# SN74ALVC164245_Level_Shifter.net
KiCad netlist of a schematic drawn in EAGLE
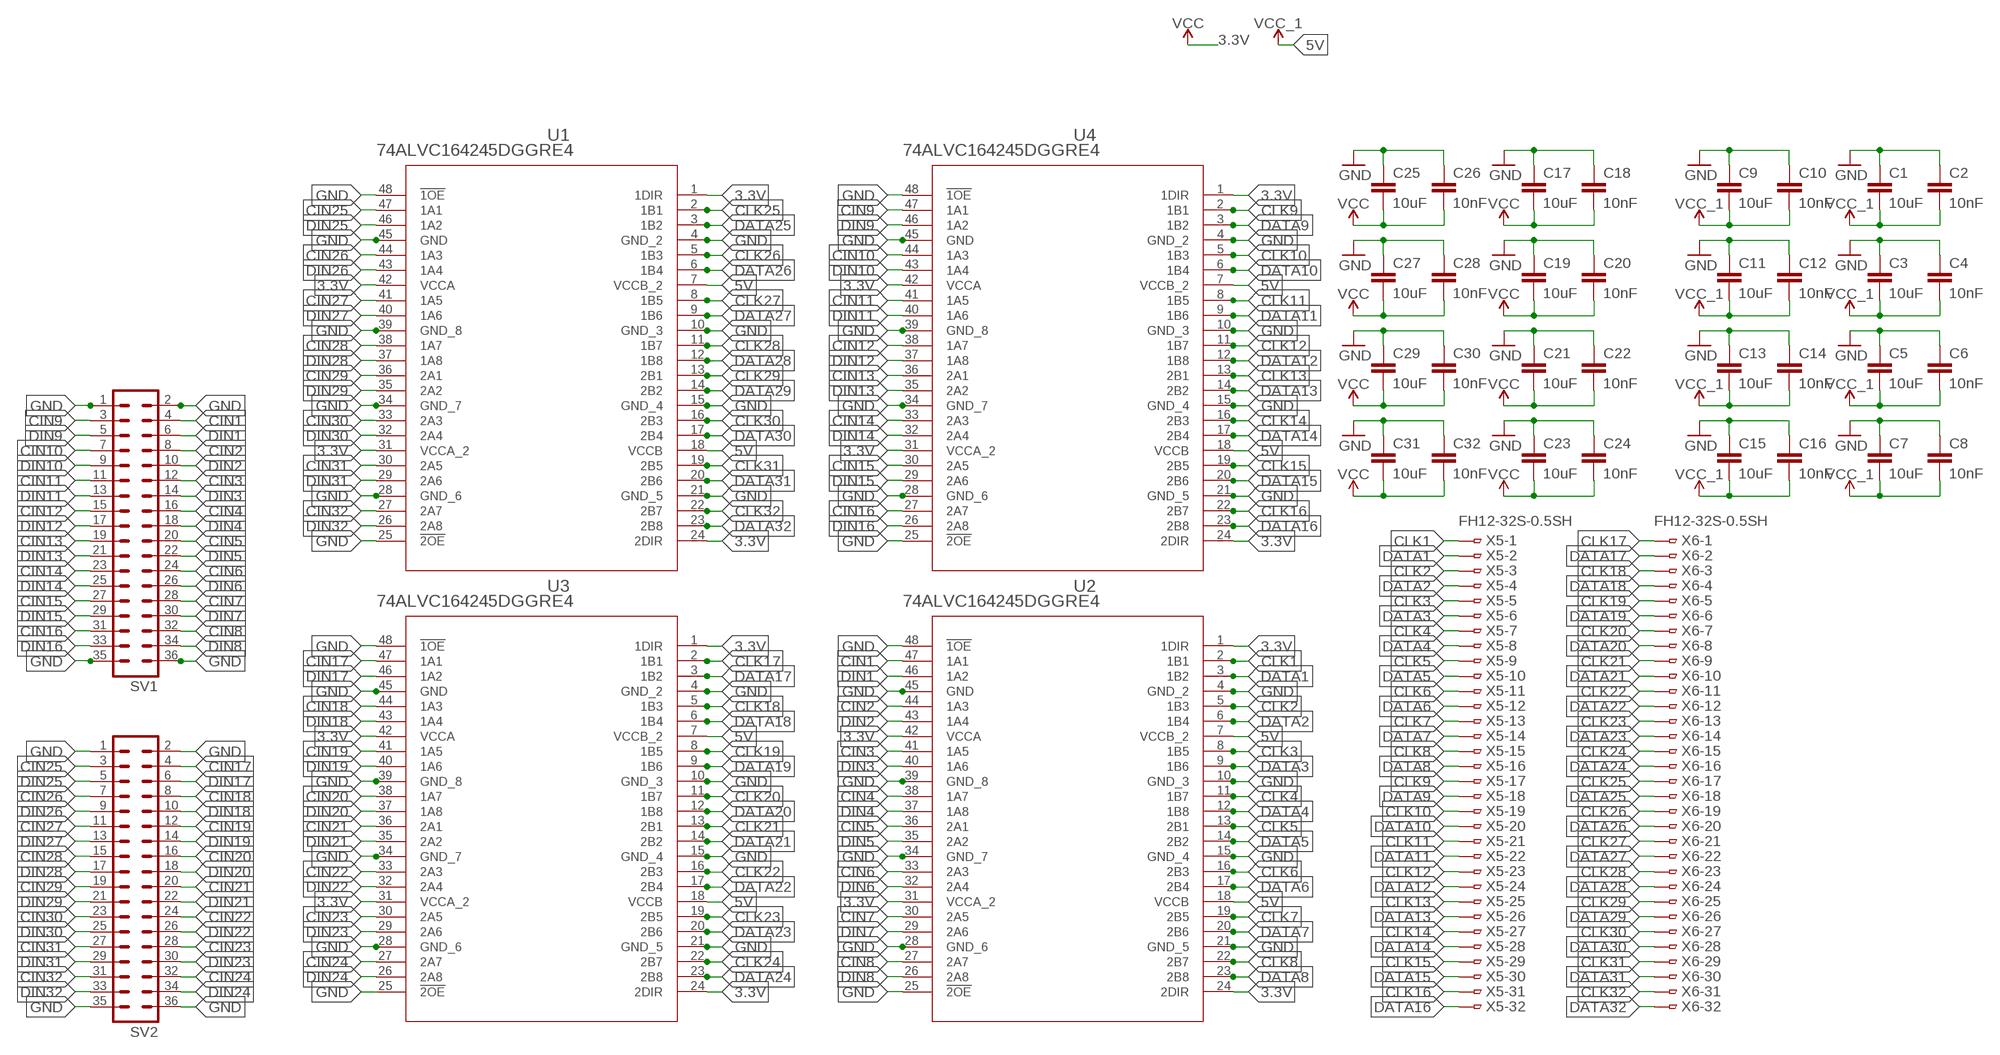
[diagram p0: schematic, sheet 1]

(export (version "E")
  (design (tool "Eeschema 10.0.6"))
  (components
    (comp (ref "C1")
      (value "10uF")
      (footprint "eagle-import:0402-TIGHT")
      (libsource (lib "eagle-import") (part "10UF-0402T-6.3V-20%"))
    )
    (comp (ref "C2")
      (value "10nF")
      (footprint "eagle-import:0402-TIGHT")
      (libsource (lib "eagle-import") (part "10NF-0402T-25V-10%"))
    )
    (comp (ref "C3")
      (value "10uF")
      (footprint "eagle-import:0402-TIGHT")
      (libsource (lib "eagle-import") (part "10UF-0402T-6.3V-20%"))
    )
    (comp (ref "C4")
      (value "10nF")
      (footprint "eagle-import:0402-TIGHT")
      (libsource (lib "eagle-import") (part "10NF-0402T-25V-10%"))
    )
    (comp (ref "C5")
      (value "10uF")
      (footprint "eagle-import:0402-TIGHT")
      (libsource (lib "eagle-import") (part "10UF-0402T-6.3V-20%"))
    )
    (comp (ref "C6")
      (value "10nF")
      (footprint "eagle-import:0402-TIGHT")
      (libsource (lib "eagle-import") (part "10NF-0402T-25V-10%"))
    )
    (comp (ref "C7")
      (value "10uF")
      (footprint "eagle-import:0402-TIGHT")
      (libsource (lib "eagle-import") (part "10UF-0402T-6.3V-20%"))
    )
    (comp (ref "C8")
      (value "10nF")
      (footprint "eagle-import:0402-TIGHT")
      (libsource (lib "eagle-import") (part "10NF-0402T-25V-10%"))
    )
    (comp (ref "C9")
      (value "10uF")
      (footprint "eagle-import:0402-TIGHT")
      (libsource (lib "eagle-import") (part "10UF-0402T-6.3V-20%"))
    )
    (comp (ref "C10")
      (value "10nF")
      (footprint "eagle-import:0402-TIGHT")
      (libsource (lib "eagle-import") (part "10NF-0402T-25V-10%"))
    )
    (comp (ref "C11")
      (value "10uF")
      (footprint "eagle-import:0402-TIGHT")
      (libsource (lib "eagle-import") (part "10UF-0402T-6.3V-20%"))
    )
    (comp (ref "C12")
      (value "10nF")
      (footprint "eagle-import:0402-TIGHT")
      (libsource (lib "eagle-import") (part "10NF-0402T-25V-10%"))
    )
    (comp (ref "C13")
      (value "10uF")
      (footprint "eagle-import:0402-TIGHT")
      (libsource (lib "eagle-import") (part "10UF-0402T-6.3V-20%"))
    )
    (comp (ref "C14")
      (value "10nF")
      (footprint "eagle-import:0402-TIGHT")
      (libsource (lib "eagle-import") (part "10NF-0402T-25V-10%"))
    )
    (comp (ref "C15")
      (value "10uF")
      (footprint "eagle-import:0402-TIGHT")
      (libsource (lib "eagle-import") (part "10UF-0402T-6.3V-20%"))
    )
    (comp (ref "C16")
      (value "10nF")
      (footprint "eagle-import:0402-TIGHT")
      (libsource (lib "eagle-import") (part "10NF-0402T-25V-10%"))
    )
    (comp (ref "C17")
      (value "10uF")
      (footprint "eagle-import:0402-TIGHT")
      (libsource (lib "eagle-import") (part "10UF-0402T-6.3V-20%"))
    )
    (comp (ref "C18")
      (value "10nF")
      (footprint "eagle-import:0402-TIGHT")
      (libsource (lib "eagle-import") (part "10NF-0402T-25V-10%"))
    )
    (comp (ref "C19")
      (value "10uF")
      (footprint "eagle-import:0402-TIGHT")
      (libsource (lib "eagle-import") (part "10UF-0402T-6.3V-20%"))
    )
    (comp (ref "C20")
      (value "10nF")
      (footprint "eagle-import:0402-TIGHT")
      (libsource (lib "eagle-import") (part "10NF-0402T-25V-10%"))
    )
    (comp (ref "C21")
      (value "10uF")
      (footprint "eagle-import:0402-TIGHT")
      (libsource (lib "eagle-import") (part "10UF-0402T-6.3V-20%"))
    )
    (comp (ref "C22")
      (value "10nF")
      (footprint "eagle-import:0402-TIGHT")
      (libsource (lib "eagle-import") (part "10NF-0402T-25V-10%"))
    )
    (comp (ref "C23")
      (value "10uF")
      (footprint "eagle-import:0402-TIGHT")
      (libsource (lib "eagle-import") (part "10UF-0402T-6.3V-20%"))
    )
    (comp (ref "C24")
      (value "10nF")
      (footprint "eagle-import:0402-TIGHT")
      (libsource (lib "eagle-import") (part "10NF-0402T-25V-10%"))
    )
    (comp (ref "C25")
      (value "10uF")
      (footprint "eagle-import:0402-TIGHT")
      (libsource (lib "eagle-import") (part "10UF-0402T-6.3V-20%"))
    )
    (comp (ref "C26")
      (value "10nF")
      (footprint "eagle-import:0402-TIGHT")
      (libsource (lib "eagle-import") (part "10NF-0402T-25V-10%"))
    )
    (comp (ref "C27")
      (value "10uF")
      (footprint "eagle-import:0402-TIGHT")
      (libsource (lib "eagle-import") (part "10UF-0402T-6.3V-20%"))
    )
    (comp (ref "C28")
      (value "10nF")
      (footprint "eagle-import:0402-TIGHT")
      (libsource (lib "eagle-import") (part "10NF-0402T-25V-10%"))
    )
    (comp (ref "C29")
      (value "10uF")
      (footprint "eagle-import:0402-TIGHT")
      (libsource (lib "eagle-import") (part "10UF-0402T-6.3V-20%"))
    )
    (comp (ref "C30")
      (value "10nF")
      (footprint "eagle-import:0402-TIGHT")
      (libsource (lib "eagle-import") (part "10NF-0402T-25V-10%"))
    )
    (comp (ref "C31")
      (value "10uF")
      (footprint "eagle-import:0402-TIGHT")
      (libsource (lib "eagle-import") (part "10UF-0402T-6.3V-20%"))
    )
    (comp (ref "C32")
      (value "10nF")
      (footprint "eagle-import:0402-TIGHT")
      (libsource (lib "eagle-import") (part "10NF-0402T-25V-10%"))
    )
    (comp (ref "SV1")
      (value "MA18-2")
      (footprint "eagle-import:MA18-2")
      (libsource (lib "eagle-import") (part "MA18-2"))
    )
    (comp (ref "SV2")
      (value "MA18-2")
      (footprint "eagle-import:MA18-2")
      (libsource (lib "eagle-import") (part "MA18-2"))
    )
    (comp (ref "U1")
      (value "74ALVC164245DGGRE4")
      (footprint "eagle-import:DGG48")
      (fields
        (field (name "GENERIC_PART_NUMBER") "SN74ALVC164245")
        (field (name "MANUFACTURER") "Texas Instruments")
      )
      (libsource (lib "eagle-import") (part "74ALVC164245DGGRE4"))
    )
    (comp (ref "U2")
      (value "74ALVC164245DGGRE4")
      (footprint "eagle-import:DGG48")
      (fields
        (field (name "GENERIC_PART_NUMBER") "SN74ALVC164245")
        (field (name "MANUFACTURER") "Texas Instruments")
      )
      (libsource (lib "eagle-import") (part "74ALVC164245DGGRE4"))
    )
    (comp (ref "U3")
      (value "74ALVC164245DGGRE4")
      (footprint "eagle-import:DGG48")
      (fields
        (field (name "GENERIC_PART_NUMBER") "SN74ALVC164245")
        (field (name "MANUFACTURER") "Texas Instruments")
      )
      (libsource (lib "eagle-import") (part "74ALVC164245DGGRE4"))
    )
    (comp (ref "U4")
      (value "74ALVC164245DGGRE4")
      (footprint "eagle-import:DGG48")
      (fields
        (field (name "GENERIC_PART_NUMBER") "SN74ALVC164245")
        (field (name "MANUFACTURER") "Texas Instruments")
      )
      (libsource (lib "eagle-import") (part "74ALVC164245DGGRE4"))
    )
    (comp (ref "X5")
      (value "FH12-32S-0.5SH")
      (footprint "eagle-import:FH12-32S-0.5SH")
      (libsource (lib "eagle-import") (part "FH12-32S-0.5SH"))
    )
    (comp (ref "X6")
      (value "FH12-32S-0.5SH")
      (footprint "eagle-import:FH12-32S-0.5SH")
      (libsource (lib "eagle-import") (part "FH12-32S-0.5SH"))
    )
  )
  (nets
    (net (code "1") (name "3.3V") (class "Default")
      (node (ref "C17") (pin "2") (pinfunction "2_2") (pintype "passive"))
      (node (ref "C18") (pin "2") (pinfunction "2_2") (pintype "passive"))
      (node (ref "C19") (pin "2") (pinfunction "2_2") (pintype "passive"))
      (node (ref "C20") (pin "2") (pinfunction "2_2") (pintype "passive"))
      (node (ref "C21") (pin "2") (pinfunction "2_2") (pintype "passive"))
      (node (ref "C22") (pin "2") (pinfunction "2_2") (pintype "passive"))
      (node (ref "C23") (pin "2") (pinfunction "2_2") (pintype "passive"))
      (node (ref "C24") (pin "2") (pinfunction "2_2") (pintype "passive"))
      (node (ref "C25") (pin "2") (pinfunction "2_2") (pintype "passive"))
      (node (ref "C26") (pin "2") (pinfunction "2_2") (pintype "passive"))
      (node (ref "C27") (pin "2") (pinfunction "2_2") (pintype "passive"))
      (node (ref "C28") (pin "2") (pinfunction "2_2") (pintype "passive"))
      (node (ref "C29") (pin "2") (pinfunction "2_2") (pintype "passive"))
      (node (ref "C30") (pin "2") (pinfunction "2_2") (pintype "passive"))
      (node (ref "C31") (pin "2") (pinfunction "2_2") (pintype "passive"))
      (node (ref "C32") (pin "2") (pinfunction "2_2") (pintype "passive"))
      (node (ref "U1") (pin "1") (pinfunction "1DIR_1") (pintype "input"))
      (node (ref "U1") (pin "24") (pinfunction "2DIR_24") (pintype "input"))
      (node (ref "U1") (pin "31") (pinfunction "VCCA_2_31") (pintype "power_in"))
      (node (ref "U1") (pin "42") (pinfunction "VCCA_42") (pintype "power_in"))
      (node (ref "U2") (pin "1") (pinfunction "1DIR_1") (pintype "input"))
      (node (ref "U2") (pin "24") (pinfunction "2DIR_24") (pintype "input"))
      (node (ref "U2") (pin "31") (pinfunction "VCCA_2_31") (pintype "power_in"))
      (node (ref "U2") (pin "42") (pinfunction "VCCA_42") (pintype "power_in"))
      (node (ref "U3") (pin "1") (pinfunction "1DIR_1") (pintype "input"))
      (node (ref "U3") (pin "24") (pinfunction "2DIR_24") (pintype "input"))
      (node (ref "U3") (pin "31") (pinfunction "VCCA_2_31") (pintype "power_in"))
      (node (ref "U3") (pin "42") (pinfunction "VCCA_42") (pintype "power_in"))
      (node (ref "U4") (pin "1") (pinfunction "1DIR_1") (pintype "input"))
      (node (ref "U4") (pin "24") (pinfunction "2DIR_24") (pintype "input"))
      (node (ref "U4") (pin "31") (pinfunction "VCCA_2_31") (pintype "power_in"))
      (node (ref "U4") (pin "42") (pinfunction "VCCA_42") (pintype "power_in"))
    )
    (net (code "2") (name "5V") (class "Default")
      (node (ref "C1") (pin "2") (pinfunction "2_2") (pintype "passive"))
      (node (ref "C10") (pin "2") (pinfunction "2_2") (pintype "passive"))
      (node (ref "C11") (pin "2") (pinfunction "2_2") (pintype "passive"))
      (node (ref "C12") (pin "2") (pinfunction "2_2") (pintype "passive"))
      (node (ref "C13") (pin "2") (pinfunction "2_2") (pintype "passive"))
      (node (ref "C14") (pin "2") (pinfunction "2_2") (pintype "passive"))
      (node (ref "C15") (pin "2") (pinfunction "2_2") (pintype "passive"))
      (node (ref "C16") (pin "2") (pinfunction "2_2") (pintype "passive"))
      (node (ref "C2") (pin "2") (pinfunction "2_2") (pintype "passive"))
      (node (ref "C3") (pin "2") (pinfunction "2_2") (pintype "passive"))
      (node (ref "C4") (pin "2") (pinfunction "2_2") (pintype "passive"))
      (node (ref "C5") (pin "2") (pinfunction "2_2") (pintype "passive"))
      (node (ref "C6") (pin "2") (pinfunction "2_2") (pintype "passive"))
      (node (ref "C7") (pin "2") (pinfunction "2_2") (pintype "passive"))
      (node (ref "C8") (pin "2") (pinfunction "2_2") (pintype "passive"))
      (node (ref "C9") (pin "2") (pinfunction "2_2") (pintype "passive"))
      (node (ref "U1") (pin "18") (pinfunction "VCCB_18") (pintype "power_in"))
      (node (ref "U1") (pin "7") (pinfunction "VCCB_2_7") (pintype "power_in"))
      (node (ref "U2") (pin "18") (pinfunction "VCCB_18") (pintype "power_in"))
      (node (ref "U2") (pin "7") (pinfunction "VCCB_2_7") (pintype "power_in"))
      (node (ref "U3") (pin "18") (pinfunction "VCCB_18") (pintype "power_in"))
      (node (ref "U3") (pin "7") (pinfunction "VCCB_2_7") (pintype "power_in"))
      (node (ref "U4") (pin "18") (pinfunction "VCCB_18") (pintype "power_in"))
      (node (ref "U4") (pin "7") (pinfunction "VCCB_2_7") (pintype "power_in"))
    )
    (net (code "3") (name "CIN1") (class "Default")
      (node (ref "SV1") (pin "4") (pinfunction "4_4") (pintype "passive"))
      (node (ref "U2") (pin "47") (pinfunction "1A1_47") (pintype "bidirectional"))
    )
    (net (code "4") (name "CIN2") (class "Default")
      (node (ref "SV1") (pin "8") (pinfunction "8_8") (pintype "passive"))
      (node (ref "U2") (pin "44") (pinfunction "1A3_44") (pintype "bidirectional"))
    )
    (net (code "5") (name "CIN3") (class "Default")
      (node (ref "SV1") (pin "12") (pinfunction "12_12") (pintype "passive"))
      (node (ref "U2") (pin "41") (pinfunction "1A5_41") (pintype "bidirectional"))
    )
    (net (code "6") (name "CIN4") (class "Default")
      (node (ref "SV1") (pin "16") (pinfunction "16_16") (pintype "passive"))
      (node (ref "U2") (pin "38") (pinfunction "1A7_38") (pintype "bidirectional"))
    )
    (net (code "7") (name "CIN5") (class "Default")
      (node (ref "SV1") (pin "20") (pinfunction "20_20") (pintype "passive"))
      (node (ref "U2") (pin "36") (pinfunction "2A1_36") (pintype "bidirectional"))
    )
    (net (code "8") (name "CIN6") (class "Default")
      (node (ref "SV1") (pin "24") (pinfunction "24_24") (pintype "passive"))
      (node (ref "U2") (pin "33") (pinfunction "2A3_33") (pintype "bidirectional"))
    )
    (net (code "9") (name "CIN7") (class "Default")
      (node (ref "SV1") (pin "28") (pinfunction "28_28") (pintype "passive"))
      (node (ref "U2") (pin "30") (pinfunction "2A5_30") (pintype "bidirectional"))
    )
    (net (code "10") (name "CIN8") (class "Default")
      (node (ref "SV1") (pin "32") (pinfunction "32_32") (pintype "passive"))
      (node (ref "U2") (pin "27") (pinfunction "2A7_27") (pintype "bidirectional"))
    )
    (net (code "11") (name "CIN9") (class "Default")
      (node (ref "SV1") (pin "3") (pinfunction "3_3") (pintype "passive"))
      (node (ref "U4") (pin "47") (pinfunction "1A1_47") (pintype "bidirectional"))
    )
    (net (code "12") (name "CIN10") (class "Default")
      (node (ref "SV1") (pin "7") (pinfunction "7_7") (pintype "passive"))
      (node (ref "U4") (pin "44") (pinfunction "1A3_44") (pintype "bidirectional"))
    )
    (net (code "13") (name "CIN11") (class "Default")
      (node (ref "SV1") (pin "11") (pinfunction "11_11") (pintype "passive"))
      (node (ref "U4") (pin "41") (pinfunction "1A5_41") (pintype "bidirectional"))
    )
    (net (code "14") (name "CIN12") (class "Default")
      (node (ref "SV1") (pin "15") (pinfunction "15_15") (pintype "passive"))
      (node (ref "U4") (pin "38") (pinfunction "1A7_38") (pintype "bidirectional"))
    )
    (net (code "15") (name "CIN13") (class "Default")
      (node (ref "SV1") (pin "19") (pinfunction "19_19") (pintype "passive"))
      (node (ref "U4") (pin "36") (pinfunction "2A1_36") (pintype "bidirectional"))
    )
    (net (code "16") (name "CIN14") (class "Default")
      (node (ref "SV1") (pin "23") (pinfunction "23_23") (pintype "passive"))
      (node (ref "U4") (pin "33") (pinfunction "2A3_33") (pintype "bidirectional"))
    )
    (net (code "17") (name "CIN15") (class "Default")
      (node (ref "SV1") (pin "27") (pinfunction "27_27") (pintype "passive"))
      (node (ref "U4") (pin "30") (pinfunction "2A5_30") (pintype "bidirectional"))
    )
    (net (code "18") (name "CIN16") (class "Default")
      (node (ref "SV1") (pin "31") (pinfunction "31_31") (pintype "passive"))
      (node (ref "U4") (pin "27") (pinfunction "2A7_27") (pintype "bidirectional"))
    )
    (net (code "19") (name "CIN17") (class "Default")
      (node (ref "SV2") (pin "4") (pinfunction "4_4") (pintype "passive"))
      (node (ref "U3") (pin "47") (pinfunction "1A1_47") (pintype "bidirectional"))
    )
    (net (code "20") (name "CIN18") (class "Default")
      (node (ref "SV2") (pin "8") (pinfunction "8_8") (pintype "passive"))
      (node (ref "U3") (pin "44") (pinfunction "1A3_44") (pintype "bidirectional"))
    )
    (net (code "21") (name "CIN19") (class "Default")
      (node (ref "SV2") (pin "12") (pinfunction "12_12") (pintype "passive"))
      (node (ref "U3") (pin "41") (pinfunction "1A5_41") (pintype "bidirectional"))
    )
    (net (code "22") (name "CIN20") (class "Default")
      (node (ref "SV2") (pin "16") (pinfunction "16_16") (pintype "passive"))
      (node (ref "U3") (pin "38") (pinfunction "1A7_38") (pintype "bidirectional"))
    )
    (net (code "23") (name "CIN21") (class "Default")
      (node (ref "SV2") (pin "20") (pinfunction "20_20") (pintype "passive"))
      (node (ref "U3") (pin "36") (pinfunction "2A1_36") (pintype "bidirectional"))
    )
    (net (code "24") (name "CIN22") (class "Default")
      (node (ref "SV2") (pin "24") (pinfunction "24_24") (pintype "passive"))
      (node (ref "U3") (pin "33") (pinfunction "2A3_33") (pintype "bidirectional"))
    )
    (net (code "25") (name "CIN23") (class "Default")
      (node (ref "SV2") (pin "28") (pinfunction "28_28") (pintype "passive"))
      (node (ref "U3") (pin "30") (pinfunction "2A5_30") (pintype "bidirectional"))
    )
    (net (code "26") (name "CIN24") (class "Default")
      (node (ref "SV2") (pin "32") (pinfunction "32_32") (pintype "passive"))
      (node (ref "U3") (pin "27") (pinfunction "2A7_27") (pintype "bidirectional"))
    )
    (net (code "27") (name "CIN25") (class "Default")
      (node (ref "SV2") (pin "3") (pinfunction "3_3") (pintype "passive"))
      (node (ref "U1") (pin "47") (pinfunction "1A1_47") (pintype "bidirectional"))
    )
    (net (code "28") (name "CIN26") (class "Default")
      (node (ref "SV2") (pin "7") (pinfunction "7_7") (pintype "passive"))
      (node (ref "U1") (pin "44") (pinfunction "1A3_44") (pintype "bidirectional"))
    )
    (net (code "29") (name "CIN27") (class "Default")
      (node (ref "SV2") (pin "11") (pinfunction "11_11") (pintype "passive"))
      (node (ref "U1") (pin "41") (pinfunction "1A5_41") (pintype "bidirectional"))
    )
    (net (code "30") (name "CIN28") (class "Default")
      (node (ref "SV2") (pin "15") (pinfunction "15_15") (pintype "passive"))
      (node (ref "U1") (pin "38") (pinfunction "1A7_38") (pintype "bidirectional"))
    )
    (net (code "31") (name "CIN29") (class "Default")
      (node (ref "SV2") (pin "19") (pinfunction "19_19") (pintype "passive"))
      (node (ref "U1") (pin "36") (pinfunction "2A1_36") (pintype "bidirectional"))
    )
    (net (code "32") (name "CIN30") (class "Default")
      (node (ref "SV2") (pin "23") (pinfunction "23_23") (pintype "passive"))
      (node (ref "U1") (pin "33") (pinfunction "2A3_33") (pintype "bidirectional"))
    )
    (net (code "33") (name "CIN31") (class "Default")
      (node (ref "SV2") (pin "27") (pinfunction "27_27") (pintype "passive"))
      (node (ref "U1") (pin "30") (pinfunction "2A5_30") (pintype "bidirectional"))
    )
    (net (code "34") (name "CIN32") (class "Default")
      (node (ref "SV2") (pin "31") (pinfunction "31_31") (pintype "passive"))
      (node (ref "U1") (pin "27") (pinfunction "2A7_27") (pintype "bidirectional"))
    )
    (net (code "35") (name "CLK1") (class "Default")
      (node (ref "U2") (pin "2") (pinfunction "1B1_2") (pintype "bidirectional"))
      (node (ref "X5") (pin "1") (pinfunction "1_1") (pintype "passive"))
    )
    (net (code "36") (name "CLK2") (class "Default")
      (node (ref "U2") (pin "5") (pinfunction "1B3_5") (pintype "bidirectional"))
      (node (ref "X5") (pin "3") (pinfunction "1_3") (pintype "passive"))
    )
    (net (code "37") (name "CLK3") (class "Default")
      (node (ref "U2") (pin "8") (pinfunction "1B5_8") (pintype "bidirectional"))
      (node (ref "X5") (pin "5") (pinfunction "1_5") (pintype "passive"))
    )
    (net (code "38") (name "CLK4") (class "Default")
      (node (ref "U2") (pin "11") (pinfunction "1B7_11") (pintype "bidirectional"))
      (node (ref "X5") (pin "7") (pinfunction "1_7") (pintype "passive"))
    )
    (net (code "39") (name "CLK5") (class "Default")
      (node (ref "U2") (pin "13") (pinfunction "2B1_13") (pintype "bidirectional"))
      (node (ref "X5") (pin "9") (pinfunction "1_9") (pintype "passive"))
    )
    (net (code "40") (name "CLK6") (class "Default")
      (node (ref "U2") (pin "16") (pinfunction "2B3_16") (pintype "bidirectional"))
      (node (ref "X5") (pin "11") (pinfunction "1_11") (pintype "passive"))
    )
    (net (code "41") (name "CLK7") (class "Default")
      (node (ref "U2") (pin "19") (pinfunction "2B5_19") (pintype "bidirectional"))
      (node (ref "X5") (pin "13") (pinfunction "1_13") (pintype "passive"))
    )
    (net (code "42") (name "CLK8") (class "Default")
      (node (ref "U2") (pin "22") (pinfunction "2B7_22") (pintype "bidirectional"))
      (node (ref "X5") (pin "15") (pinfunction "1_15") (pintype "passive"))
    )
    (net (code "43") (name "CLK9") (class "Default")
      (node (ref "U4") (pin "2") (pinfunction "1B1_2") (pintype "bidirectional"))
      (node (ref "X5") (pin "17") (pinfunction "1_17") (pintype "passive"))
    )
    (net (code "44") (name "CLK10") (class "Default")
      (node (ref "U4") (pin "5") (pinfunction "1B3_5") (pintype "bidirectional"))
      (node (ref "X5") (pin "19") (pinfunction "1_19") (pintype "passive"))
    )
    (net (code "45") (name "CLK11") (class "Default")
      (node (ref "U4") (pin "8") (pinfunction "1B5_8") (pintype "bidirectional"))
      (node (ref "X5") (pin "21") (pinfunction "1_21") (pintype "passive"))
    )
    (net (code "46") (name "CLK12") (class "Default")
      (node (ref "U4") (pin "11") (pinfunction "1B7_11") (pintype "bidirectional"))
      (node (ref "X5") (pin "23") (pinfunction "1_23") (pintype "passive"))
    )
    (net (code "47") (name "CLK13") (class "Default")
      (node (ref "U4") (pin "13") (pinfunction "2B1_13") (pintype "bidirectional"))
      (node (ref "X5") (pin "25") (pinfunction "1_25") (pintype "passive"))
    )
    (net (code "48") (name "CLK14") (class "Default")
      (node (ref "U4") (pin "16") (pinfunction "2B3_16") (pintype "bidirectional"))
      (node (ref "X5") (pin "27") (pinfunction "1_27") (pintype "passive"))
    )
    (net (code "49") (name "CLK15") (class "Default")
      (node (ref "U4") (pin "19") (pinfunction "2B5_19") (pintype "bidirectional"))
      (node (ref "X5") (pin "29") (pinfunction "1_29") (pintype "passive"))
    )
    (net (code "50") (name "CLK16") (class "Default")
      (node (ref "U4") (pin "22") (pinfunction "2B7_22") (pintype "bidirectional"))
      (node (ref "X5") (pin "31") (pinfunction "1_31") (pintype "passive"))
    )
    (net (code "51") (name "CLK17") (class "Default")
      (node (ref "U3") (pin "2") (pinfunction "1B1_2") (pintype "bidirectional"))
      (node (ref "X6") (pin "1") (pinfunction "1_1") (pintype "passive"))
    )
    (net (code "52") (name "CLK18") (class "Default")
      (node (ref "U3") (pin "5") (pinfunction "1B3_5") (pintype "bidirectional"))
      (node (ref "X6") (pin "3") (pinfunction "1_3") (pintype "passive"))
    )
    (net (code "53") (name "CLK19") (class "Default")
      (node (ref "U3") (pin "8") (pinfunction "1B5_8") (pintype "bidirectional"))
      (node (ref "X6") (pin "5") (pinfunction "1_5") (pintype "passive"))
    )
    (net (code "54") (name "CLK20") (class "Default")
      (node (ref "U3") (pin "11") (pinfunction "1B7_11") (pintype "bidirectional"))
      (node (ref "X6") (pin "7") (pinfunction "1_7") (pintype "passive"))
    )
    (net (code "55") (name "CLK21") (class "Default")
      (node (ref "U3") (pin "13") (pinfunction "2B1_13") (pintype "bidirectional"))
      (node (ref "X6") (pin "9") (pinfunction "1_9") (pintype "passive"))
    )
    (net (code "56") (name "CLK22") (class "Default")
      (node (ref "U3") (pin "16") (pinfunction "2B3_16") (pintype "bidirectional"))
      (node (ref "X6") (pin "11") (pinfunction "1_11") (pintype "passive"))
    )
    (net (code "57") (name "CLK23") (class "Default")
      (node (ref "U3") (pin "19") (pinfunction "2B5_19") (pintype "bidirectional"))
      (node (ref "X6") (pin "13") (pinfunction "1_13") (pintype "passive"))
    )
    (net (code "58") (name "CLK24") (class "Default")
      (node (ref "U3") (pin "22") (pinfunction "2B7_22") (pintype "bidirectional"))
      (node (ref "X6") (pin "15") (pinfunction "1_15") (pintype "passive"))
    )
    (net (code "59") (name "CLK25") (class "Default")
      (node (ref "U1") (pin "2") (pinfunction "1B1_2") (pintype "bidirectional"))
      (node (ref "X6") (pin "17") (pinfunction "1_17") (pintype "passive"))
    )
    (net (code "60") (name "CLK26") (class "Default")
      (node (ref "U1") (pin "5") (pinfunction "1B3_5") (pintype "bidirectional"))
      (node (ref "X6") (pin "19") (pinfunction "1_19") (pintype "passive"))
    )
    (net (code "61") (name "CLK27") (class "Default")
      (node (ref "U1") (pin "8") (pinfunction "1B5_8") (pintype "bidirectional"))
      (node (ref "X6") (pin "21") (pinfunction "1_21") (pintype "passive"))
    )
    (net (code "62") (name "CLK28") (class "Default")
      (node (ref "U1") (pin "11") (pinfunction "1B7_11") (pintype "bidirectional"))
      (node (ref "X6") (pin "23") (pinfunction "1_23") (pintype "passive"))
    )
    (net (code "63") (name "CLK29") (class "Default")
      (node (ref "U1") (pin "13") (pinfunction "2B1_13") (pintype "bidirectional"))
      (node (ref "X6") (pin "25") (pinfunction "1_25") (pintype "passive"))
    )
    (net (code "64") (name "CLK30") (class "Default")
      (node (ref "U1") (pin "16") (pinfunction "2B3_16") (pintype "bidirectional"))
      (node (ref "X6") (pin "27") (pinfunction "1_27") (pintype "passive"))
    )
    (net (code "65") (name "CLK31") (class "Default")
      (node (ref "U1") (pin "19") (pinfunction "2B5_19") (pintype "bidirectional"))
      (node (ref "X6") (pin "29") (pinfunction "1_29") (pintype "passive"))
    )
    (net (code "66") (name "CLK32") (class "Default")
      (node (ref "U1") (pin "22") (pinfunction "2B7_22") (pintype "bidirectional"))
      (node (ref "X6") (pin "31") (pinfunction "1_31") (pintype "passive"))
    )
    (net (code "67") (name "DATA1") (class "Default")
      (node (ref "U2") (pin "3") (pinfunction "1B2_3") (pintype "bidirectional"))
      (node (ref "X5") (pin "2") (pinfunction "1_2") (pintype "passive"))
    )
    (net (code "68") (name "DATA2") (class "Default")
      (node (ref "U2") (pin "6") (pinfunction "1B4_6") (pintype "bidirectional"))
      (node (ref "X5") (pin "4") (pinfunction "1_4") (pintype "passive"))
    )
    (net (code "69") (name "DATA3") (class "Default")
      (node (ref "U2") (pin "9") (pinfunction "1B6_9") (pintype "bidirectional"))
      (node (ref "X5") (pin "6") (pinfunction "1_6") (pintype "passive"))
    )
    (net (code "70") (name "DATA4") (class "Default")
      (node (ref "U2") (pin "12") (pinfunction "1B8_12") (pintype "bidirectional"))
      (node (ref "X5") (pin "8") (pinfunction "1_8") (pintype "passive"))
    )
    (net (code "71") (name "DATA5") (class "Default")
      (node (ref "U2") (pin "14") (pinfunction "2B2_14") (pintype "bidirectional"))
      (node (ref "X5") (pin "10") (pinfunction "1_10") (pintype "passive"))
    )
    (net (code "72") (name "DATA6") (class "Default")
      (node (ref "U2") (pin "17") (pinfunction "2B4_17") (pintype "bidirectional"))
      (node (ref "X5") (pin "12") (pinfunction "1_12") (pintype "passive"))
    )
    (net (code "73") (name "DATA7") (class "Default")
      (node (ref "U2") (pin "20") (pinfunction "2B6_20") (pintype "bidirectional"))
      (node (ref "X5") (pin "14") (pinfunction "1_14") (pintype "passive"))
    )
    (net (code "74") (name "DATA8") (class "Default")
      (node (ref "U2") (pin "23") (pinfunction "2B8_23") (pintype "bidirectional"))
      (node (ref "X5") (pin "16") (pinfunction "1_16") (pintype "passive"))
    )
    (net (code "75") (name "DATA9") (class "Default")
      (node (ref "U4") (pin "3") (pinfunction "1B2_3") (pintype "bidirectional"))
      (node (ref "X5") (pin "18") (pinfunction "1_18") (pintype "passive"))
    )
    (net (code "76") (name "DATA10") (class "Default")
      (node (ref "U4") (pin "6") (pinfunction "1B4_6") (pintype "bidirectional"))
      (node (ref "X5") (pin "20") (pinfunction "1_20") (pintype "passive"))
    )
    (net (code "77") (name "DATA11") (class "Default")
      (node (ref "U4") (pin "9") (pinfunction "1B6_9") (pintype "bidirectional"))
      (node (ref "X5") (pin "22") (pinfunction "1_22") (pintype "passive"))
    )
    (net (code "78") (name "DATA12") (class "Default")
      (node (ref "U4") (pin "12") (pinfunction "1B8_12") (pintype "bidirectional"))
      (node (ref "X5") (pin "24") (pinfunction "1_24") (pintype "passive"))
    )
    (net (code "79") (name "DATA13") (class "Default")
      (node (ref "U4") (pin "14") (pinfunction "2B2_14") (pintype "bidirectional"))
      (node (ref "X5") (pin "26") (pinfunction "1_26") (pintype "passive"))
    )
    (net (code "80") (name "DATA14") (class "Default")
      (node (ref "U4") (pin "17") (pinfunction "2B4_17") (pintype "bidirectional"))
      (node (ref "X5") (pin "28") (pinfunction "1_28") (pintype "passive"))
    )
    (net (code "81") (name "DATA15") (class "Default")
      (node (ref "U4") (pin "20") (pinfunction "2B6_20") (pintype "bidirectional"))
      (node (ref "X5") (pin "30") (pinfunction "1_30") (pintype "passive"))
    )
    (net (code "82") (name "DATA16") (class "Default")
      (node (ref "U4") (pin "23") (pinfunction "2B8_23") (pintype "bidirectional"))
      (node (ref "X5") (pin "32") (pinfunction "1_32") (pintype "passive"))
    )
    (net (code "83") (name "DATA17") (class "Default")
      (node (ref "U3") (pin "3") (pinfunction "1B2_3") (pintype "bidirectional"))
      (node (ref "X6") (pin "2") (pinfunction "1_2") (pintype "passive"))
    )
    (net (code "84") (name "DATA18") (class "Default")
      (node (ref "U3") (pin "6") (pinfunction "1B4_6") (pintype "bidirectional"))
      (node (ref "X6") (pin "4") (pinfunction "1_4") (pintype "passive"))
    )
    (net (code "85") (name "DATA19") (class "Default")
      (node (ref "U3") (pin "9") (pinfunction "1B6_9") (pintype "bidirectional"))
      (node (ref "X6") (pin "6") (pinfunction "1_6") (pintype "passive"))
    )
    (net (code "86") (name "DATA20") (class "Default")
      (node (ref "U3") (pin "12") (pinfunction "1B8_12") (pintype "bidirectional"))
      (node (ref "X6") (pin "8") (pinfunction "1_8") (pintype "passive"))
    )
    (net (code "87") (name "DATA21") (class "Default")
      (node (ref "U3") (pin "14") (pinfunction "2B2_14") (pintype "bidirectional"))
      (node (ref "X6") (pin "10") (pinfunction "1_10") (pintype "passive"))
    )
    (net (code "88") (name "DATA22") (class "Default")
      (node (ref "U3") (pin "17") (pinfunction "2B4_17") (pintype "bidirectional"))
      (node (ref "X6") (pin "12") (pinfunction "1_12") (pintype "passive"))
    )
    (net (code "89") (name "DATA23") (class "Default")
      (node (ref "U3") (pin "20") (pinfunction "2B6_20") (pintype "bidirectional"))
      (node (ref "X6") (pin "14") (pinfunction "1_14") (pintype "passive"))
    )
    (net (code "90") (name "DATA24") (class "Default")
      (node (ref "U3") (pin "23") (pinfunction "2B8_23") (pintype "bidirectional"))
      (node (ref "X6") (pin "16") (pinfunction "1_16") (pintype "passive"))
    )
    (net (code "91") (name "DATA25") (class "Default")
      (node (ref "U1") (pin "3") (pinfunction "1B2_3") (pintype "bidirectional"))
      (node (ref "X6") (pin "18") (pinfunction "1_18") (pintype "passive"))
    )
    (net (code "92") (name "DATA26") (class "Default")
      (node (ref "U1") (pin "6") (pinfunction "1B4_6") (pintype "bidirectional"))
      (node (ref "X6") (pin "20") (pinfunction "1_20") (pintype "passive"))
    )
    (net (code "93") (name "DATA27") (class "Default")
      (node (ref "U1") (pin "9") (pinfunction "1B6_9") (pintype "bidirectional"))
      (node (ref "X6") (pin "22") (pinfunction "1_22") (pintype "passive"))
    )
    (net (code "94") (name "DATA28") (class "Default")
      (node (ref "U1") (pin "12") (pinfunction "1B8_12") (pintype "bidirectional"))
      (node (ref "X6") (pin "24") (pinfunction "1_24") (pintype "passive"))
    )
    (net (code "95") (name "DATA29") (class "Default")
      (node (ref "U1") (pin "14") (pinfunction "2B2_14") (pintype "bidirectional"))
      (node (ref "X6") (pin "26") (pinfunction "1_26") (pintype "passive"))
    )
    (net (code "96") (name "DATA30") (class "Default")
      (node (ref "U1") (pin "17") (pinfunction "2B4_17") (pintype "bidirectional"))
      (node (ref "X6") (pin "28") (pinfunction "1_28") (pintype "passive"))
    )
    (net (code "97") (name "DATA31") (class "Default")
      (node (ref "U1") (pin "20") (pinfunction "2B6_20") (pintype "bidirectional"))
      (node (ref "X6") (pin "30") (pinfunction "1_30") (pintype "passive"))
    )
    (net (code "98") (name "DATA32") (class "Default")
      (node (ref "U1") (pin "23") (pinfunction "2B8_23") (pintype "bidirectional"))
      (node (ref "X6") (pin "32") (pinfunction "1_32") (pintype "passive"))
    )
    (net (code "99") (name "DIN1") (class "Default")
      (node (ref "SV1") (pin "6") (pinfunction "6_6") (pintype "passive"))
      (node (ref "U2") (pin "46") (pinfunction "1A2_46") (pintype "bidirectional"))
    )
    (net (code "100") (name "DIN2") (class "Default")
      (node (ref "SV1") (pin "10") (pinfunction "10_10") (pintype "passive"))
      (node (ref "U2") (pin "43") (pinfunction "1A4_43") (pintype "bidirectional"))
    )
    (net (code "101") (name "DIN3") (class "Default")
      (node (ref "SV1") (pin "14") (pinfunction "14_14") (pintype "passive"))
      (node (ref "U2") (pin "40") (pinfunction "1A6_40") (pintype "bidirectional"))
    )
    (net (code "102") (name "DIN4") (class "Default")
      (node (ref "SV1") (pin "18") (pinfunction "18_18") (pintype "passive"))
      (node (ref "U2") (pin "37") (pinfunction "1A8_37") (pintype "bidirectional"))
    )
    (net (code "103") (name "DIN5") (class "Default")
      (node (ref "SV1") (pin "22") (pinfunction "22_22") (pintype "passive"))
      (node (ref "U2") (pin "35") (pinfunction "2A2_35") (pintype "bidirectional"))
    )
    (net (code "104") (name "DIN6") (class "Default")
      (node (ref "SV1") (pin "26") (pinfunction "26_26") (pintype "passive"))
      (node (ref "U2") (pin "32") (pinfunction "2A4_32") (pintype "bidirectional"))
    )
    (net (code "105") (name "DIN7") (class "Default")
      (node (ref "SV1") (pin "30") (pinfunction "30_30") (pintype "passive"))
      (node (ref "U2") (pin "29") (pinfunction "2A6_29") (pintype "bidirectional"))
    )
    (net (code "106") (name "DIN8") (class "Default")
      (node (ref "SV1") (pin "34") (pinfunction "34_34") (pintype "passive"))
      (node (ref "U2") (pin "26") (pinfunction "2A8_26") (pintype "bidirectional"))
    )
    (net (code "107") (name "DIN9") (class "Default")
      (node (ref "SV1") (pin "5") (pinfunction "5_5") (pintype "passive"))
      (node (ref "U4") (pin "46") (pinfunction "1A2_46") (pintype "bidirectional"))
    )
    (net (code "108") (name "DIN10") (class "Default")
      (node (ref "SV1") (pin "9") (pinfunction "9_9") (pintype "passive"))
      (node (ref "U4") (pin "43") (pinfunction "1A4_43") (pintype "bidirectional"))
    )
    (net (code "109") (name "DIN11") (class "Default")
      (node (ref "SV1") (pin "13") (pinfunction "13_13") (pintype "passive"))
      (node (ref "U4") (pin "40") (pinfunction "1A6_40") (pintype "bidirectional"))
    )
    (net (code "110") (name "DIN12") (class "Default")
      (node (ref "SV1") (pin "17") (pinfunction "17_17") (pintype "passive"))
      (node (ref "U4") (pin "37") (pinfunction "1A8_37") (pintype "bidirectional"))
    )
    (net (code "111") (name "DIN13") (class "Default")
      (node (ref "SV1") (pin "21") (pinfunction "21_21") (pintype "passive"))
      (node (ref "U4") (pin "35") (pinfunction "2A2_35") (pintype "bidirectional"))
    )
    (net (code "112") (name "DIN14") (class "Default")
      (node (ref "SV1") (pin "25") (pinfunction "25_25") (pintype "passive"))
      (node (ref "U4") (pin "32") (pinfunction "2A4_32") (pintype "bidirectional"))
    )
    (net (code "113") (name "DIN15") (class "Default")
      (node (ref "SV1") (pin "29") (pinfunction "29_29") (pintype "passive"))
      (node (ref "U4") (pin "29") (pinfunction "2A6_29") (pintype "bidirectional"))
    )
    (net (code "114") (name "DIN16") (class "Default")
      (node (ref "SV1") (pin "33") (pinfunction "33_33") (pintype "passive"))
      (node (ref "U4") (pin "26") (pinfunction "2A8_26") (pintype "bidirectional"))
    )
    (net (code "115") (name "DIN17") (class "Default")
      (node (ref "SV2") (pin "6") (pinfunction "6_6") (pintype "passive"))
      (node (ref "U3") (pin "46") (pinfunction "1A2_46") (pintype "bidirectional"))
    )
    (net (code "116") (name "DIN18") (class "Default")
      (node (ref "SV2") (pin "10") (pinfunction "10_10") (pintype "passive"))
      (node (ref "U3") (pin "43") (pinfunction "1A4_43") (pintype "bidirectional"))
    )
    (net (code "117") (name "DIN19") (class "Default")
      (node (ref "SV2") (pin "14") (pinfunction "14_14") (pintype "passive"))
      (node (ref "U3") (pin "40") (pinfunction "1A6_40") (pintype "bidirectional"))
    )
    (net (code "118") (name "DIN20") (class "Default")
      (node (ref "SV2") (pin "18") (pinfunction "18_18") (pintype "passive"))
      (node (ref "U3") (pin "37") (pinfunction "1A8_37") (pintype "bidirectional"))
    )
    (net (code "119") (name "DIN21") (class "Default")
      (node (ref "SV2") (pin "22") (pinfunction "22_22") (pintype "passive"))
      (node (ref "U3") (pin "35") (pinfunction "2A2_35") (pintype "bidirectional"))
    )
    (net (code "120") (name "DIN22") (class "Default")
      (node (ref "SV2") (pin "26") (pinfunction "26_26") (pintype "passive"))
      (node (ref "U3") (pin "32") (pinfunction "2A4_32") (pintype "bidirectional"))
    )
    (net (code "121") (name "DIN23") (class "Default")
      (node (ref "SV2") (pin "30") (pinfunction "30_30") (pintype "passive"))
      (node (ref "U3") (pin "29") (pinfunction "2A6_29") (pintype "bidirectional"))
    )
    (net (code "122") (name "DIN24") (class "Default")
      (node (ref "SV2") (pin "34") (pinfunction "34_34") (pintype "passive"))
      (node (ref "U3") (pin "26") (pinfunction "2A8_26") (pintype "bidirectional"))
    )
    (net (code "123") (name "DIN25") (class "Default")
      (node (ref "SV2") (pin "5") (pinfunction "5_5") (pintype "passive"))
      (node (ref "U1") (pin "46") (pinfunction "1A2_46") (pintype "bidirectional"))
    )
    (net (code "124") (name "DIN26") (class "Default")
      (node (ref "SV2") (pin "9") (pinfunction "9_9") (pintype "passive"))
      (node (ref "U1") (pin "43") (pinfunction "1A4_43") (pintype "bidirectional"))
    )
    (net (code "125") (name "DIN27") (class "Default")
      (node (ref "SV2") (pin "13") (pinfunction "13_13") (pintype "passive"))
      (node (ref "U1") (pin "40") (pinfunction "1A6_40") (pintype "bidirectional"))
    )
    (net (code "126") (name "DIN28") (class "Default")
      (node (ref "SV2") (pin "17") (pinfunction "17_17") (pintype "passive"))
      (node (ref "U1") (pin "37") (pinfunction "1A8_37") (pintype "bidirectional"))
    )
    (net (code "127") (name "DIN29") (class "Default")
      (node (ref "SV2") (pin "21") (pinfunction "21_21") (pintype "passive"))
      (node (ref "U1") (pin "35") (pinfunction "2A2_35") (pintype "bidirectional"))
    )
    (net (code "128") (name "DIN30") (class "Default")
      (node (ref "SV2") (pin "25") (pinfunction "25_25") (pintype "passive"))
      (node (ref "U1") (pin "32") (pinfunction "2A4_32") (pintype "bidirectional"))
    )
    (net (code "129") (name "DIN31") (class "Default")
      (node (ref "SV2") (pin "29") (pinfunction "29_29") (pintype "passive"))
      (node (ref "U1") (pin "29") (pinfunction "2A6_29") (pintype "bidirectional"))
    )
    (net (code "130") (name "DIN32") (class "Default")
      (node (ref "SV2") (pin "33") (pinfunction "33_33") (pintype "passive"))
      (node (ref "U1") (pin "26") (pinfunction "2A8_26") (pintype "bidirectional"))
    )
    (net (code "131") (name "GND") (class "Default")
      (node (ref "C1") (pin "1") (pinfunction "1_1") (pintype "passive"))
      (node (ref "C10") (pin "1") (pinfunction "1_1") (pintype "passive"))
      (node (ref "C11") (pin "1") (pinfunction "1_1") (pintype "passive"))
      (node (ref "C12") (pin "1") (pinfunction "1_1") (pintype "passive"))
      (node (ref "C13") (pin "1") (pinfunction "1_1") (pintype "passive"))
      (node (ref "C14") (pin "1") (pinfunction "1_1") (pintype "passive"))
      (node (ref "C15") (pin "1") (pinfunction "1_1") (pintype "passive"))
      (node (ref "C16") (pin "1") (pinfunction "1_1") (pintype "passive"))
      (node (ref "C17") (pin "1") (pinfunction "1_1") (pintype "passive"))
      (node (ref "C18") (pin "1") (pinfunction "1_1") (pintype "passive"))
      (node (ref "C19") (pin "1") (pinfunction "1_1") (pintype "passive"))
      (node (ref "C2") (pin "1") (pinfunction "1_1") (pintype "passive"))
      (node (ref "C20") (pin "1") (pinfunction "1_1") (pintype "passive"))
      (node (ref "C21") (pin "1") (pinfunction "1_1") (pintype "passive"))
      (node (ref "C22") (pin "1") (pinfunction "1_1") (pintype "passive"))
      (node (ref "C23") (pin "1") (pinfunction "1_1") (pintype "passive"))
      (node (ref "C24") (pin "1") (pinfunction "1_1") (pintype "passive"))
      (node (ref "C25") (pin "1") (pinfunction "1_1") (pintype "passive"))
      (node (ref "C26") (pin "1") (pinfunction "1_1") (pintype "passive"))
      (node (ref "C27") (pin "1") (pinfunction "1_1") (pintype "passive"))
      (node (ref "C28") (pin "1") (pinfunction "1_1") (pintype "passive"))
      (node (ref "C29") (pin "1") (pinfunction "1_1") (pintype "passive"))
      (node (ref "C3") (pin "1") (pinfunction "1_1") (pintype "passive"))
      (node (ref "C30") (pin "1") (pinfunction "1_1") (pintype "passive"))
      (node (ref "C31") (pin "1") (pinfunction "1_1") (pintype "passive"))
      (node (ref "C32") (pin "1") (pinfunction "1_1") (pintype "passive"))
      (node (ref "C4") (pin "1") (pinfunction "1_1") (pintype "passive"))
      (node (ref "C5") (pin "1") (pinfunction "1_1") (pintype "passive"))
      (node (ref "C6") (pin "1") (pinfunction "1_1") (pintype "passive"))
      (node (ref "C7") (pin "1") (pinfunction "1_1") (pintype "passive"))
      (node (ref "C8") (pin "1") (pinfunction "1_1") (pintype "passive"))
      (node (ref "C9") (pin "1") (pinfunction "1_1") (pintype "passive"))
      (node (ref "SV1") (pin "1") (pinfunction "1_1") (pintype "passive"))
      (node (ref "SV1") (pin "2") (pinfunction "2_2") (pintype "passive"))
      (node (ref "SV1") (pin "35") (pinfunction "35_35") (pintype "passive"))
      (node (ref "SV1") (pin "36") (pinfunction "36_36") (pintype "passive"))
      (node (ref "SV2") (pin "1") (pinfunction "1_1") (pintype "passive"))
      (node (ref "SV2") (pin "2") (pinfunction "2_2") (pintype "passive"))
      (node (ref "SV2") (pin "35") (pinfunction "35_35") (pintype "passive"))
      (node (ref "SV2") (pin "36") (pinfunction "36_36") (pintype "passive"))
      (node (ref "U1") (pin "10") (pinfunction "GND_3_10") (pintype "power_in"))
      (node (ref "U1") (pin "15") (pinfunction "GND_4_15") (pintype "power_in"))
      (node (ref "U1") (pin "21") (pinfunction "GND_5_21") (pintype "power_in"))
      (node (ref "U1") (pin "25") (pinfunction "~{2OE}_25") (pintype "input"))
      (node (ref "U1") (pin "28") (pinfunction "GND_6_28") (pintype "power_in"))
      (node (ref "U1") (pin "34") (pinfunction "GND_7_34") (pintype "power_in"))
      (node (ref "U1") (pin "39") (pinfunction "GND_8_39") (pintype "power_in"))
      (node (ref "U1") (pin "4") (pinfunction "GND_2_4") (pintype "power_in"))
      (node (ref "U1") (pin "45") (pinfunction "GND_45") (pintype "power_in"))
      (node (ref "U1") (pin "48") (pinfunction "~{1OE}_48") (pintype "input"))
      (node (ref "U2") (pin "10") (pinfunction "GND_3_10") (pintype "power_in"))
      (node (ref "U2") (pin "15") (pinfunction "GND_4_15") (pintype "power_in"))
      (node (ref "U2") (pin "21") (pinfunction "GND_5_21") (pintype "power_in"))
      (node (ref "U2") (pin "25") (pinfunction "~{2OE}_25") (pintype "input"))
      (node (ref "U2") (pin "28") (pinfunction "GND_6_28") (pintype "power_in"))
      (node (ref "U2") (pin "34") (pinfunction "GND_7_34") (pintype "power_in"))
      (node (ref "U2") (pin "39") (pinfunction "GND_8_39") (pintype "power_in"))
      (node (ref "U2") (pin "4") (pinfunction "GND_2_4") (pintype "power_in"))
      (node (ref "U2") (pin "45") (pinfunction "GND_45") (pintype "power_in"))
      (node (ref "U2") (pin "48") (pinfunction "~{1OE}_48") (pintype "input"))
      (node (ref "U3") (pin "10") (pinfunction "GND_3_10") (pintype "power_in"))
      (node (ref "U3") (pin "15") (pinfunction "GND_4_15") (pintype "power_in"))
      (node (ref "U3") (pin "21") (pinfunction "GND_5_21") (pintype "power_in"))
      (node (ref "U3") (pin "25") (pinfunction "~{2OE}_25") (pintype "input"))
      (node (ref "U3") (pin "28") (pinfunction "GND_6_28") (pintype "power_in"))
      (node (ref "U3") (pin "34") (pinfunction "GND_7_34") (pintype "power_in"))
      (node (ref "U3") (pin "39") (pinfunction "GND_8_39") (pintype "power_in"))
      (node (ref "U3") (pin "4") (pinfunction "GND_2_4") (pintype "power_in"))
      (node (ref "U3") (pin "45") (pinfunction "GND_45") (pintype "power_in"))
      (node (ref "U3") (pin "48") (pinfunction "~{1OE}_48") (pintype "input"))
      (node (ref "U4") (pin "10") (pinfunction "GND_3_10") (pintype "power_in"))
      (node (ref "U4") (pin "15") (pinfunction "GND_4_15") (pintype "power_in"))
      (node (ref "U4") (pin "21") (pinfunction "GND_5_21") (pintype "power_in"))
      (node (ref "U4") (pin "25") (pinfunction "~{2OE}_25") (pintype "input"))
      (node (ref "U4") (pin "28") (pinfunction "GND_6_28") (pintype "power_in"))
      (node (ref "U4") (pin "34") (pinfunction "GND_7_34") (pintype "power_in"))
      (node (ref "U4") (pin "39") (pinfunction "GND_8_39") (pintype "power_in"))
      (node (ref "U4") (pin "4") (pinfunction "GND_2_4") (pintype "power_in"))
      (node (ref "U4") (pin "45") (pinfunction "GND_45") (pintype "power_in"))
      (node (ref "U4") (pin "48") (pinfunction "~{1OE}_48") (pintype "input"))
    )
  )
)
